# Power_Regulators.net
KiCad netlist of a schematic drawn in Altium Designer
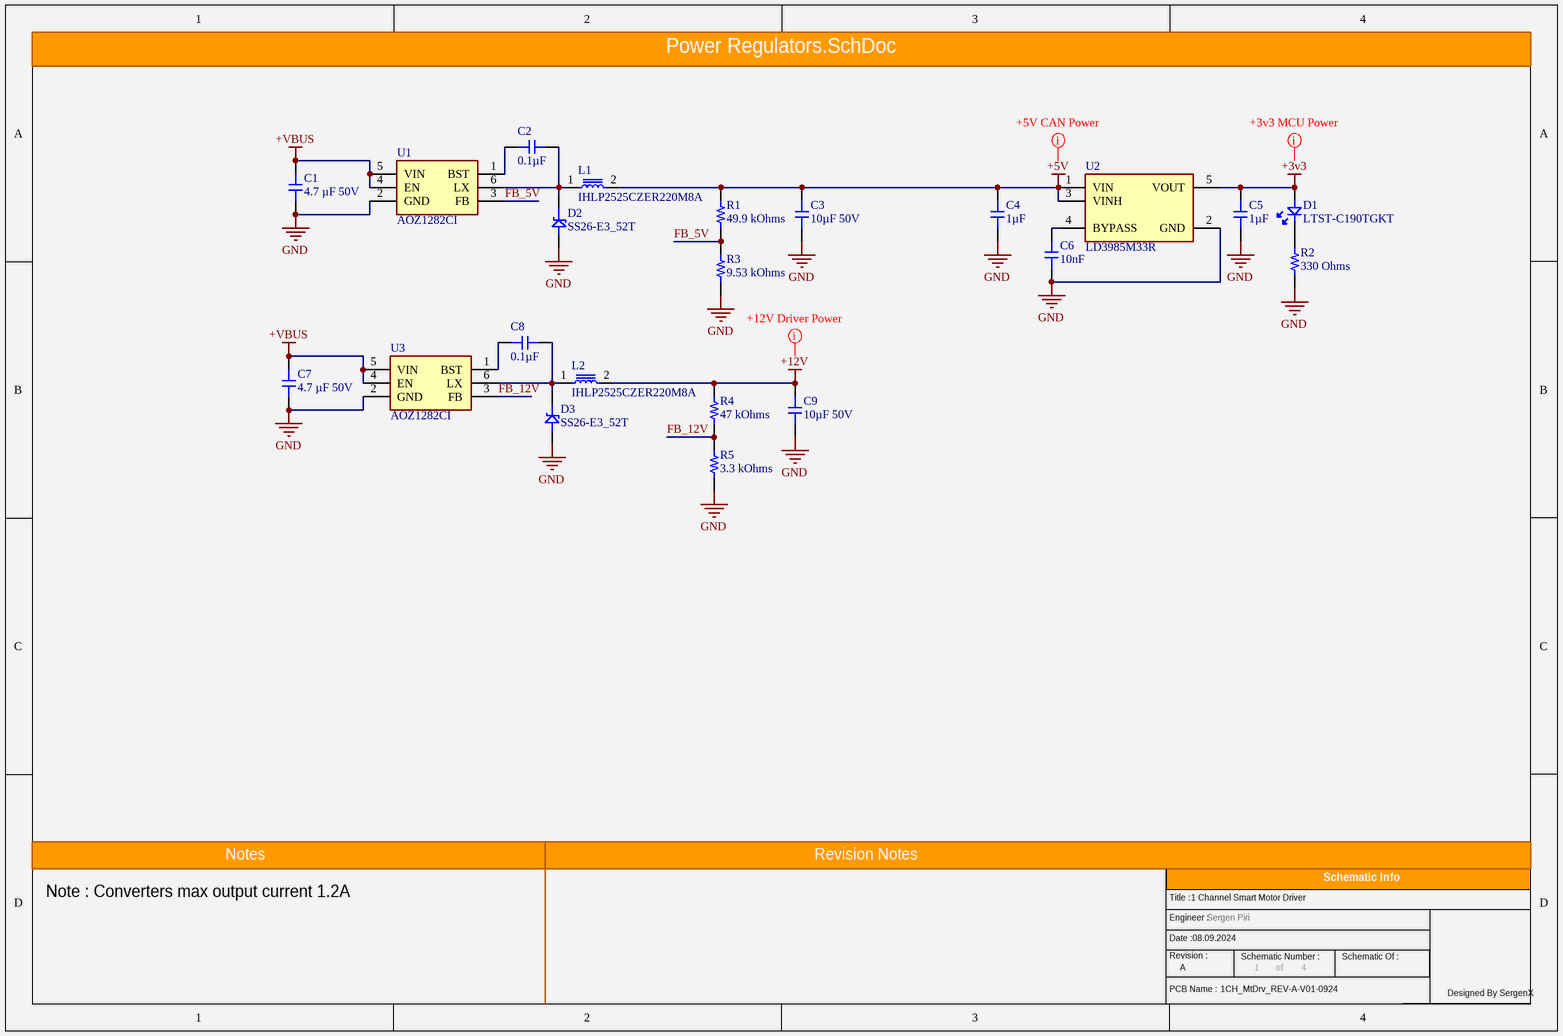
[diagram p0: Power Regulators.SchDoc]

(export (version "E")
  (design (tool "Eeschema 10.0.6"))
  (components
    (comp (ref "C1")
      (value "4.7 µF 50V")
      (footprint "1206_10uF")
      (description "10 uF 50V 1206")
      (libsource (lib "MainLibrary") (part "4.7 uF 50V 1206"))
    )
    (comp (ref "C2")
      (value "0.1µF")
      (footprint "0805")
      (description "0.1uF 0805 Surface Capacitor")
      (libsource (lib "MainLibrary") (part "0.1uF 0805 Surface Capacitor"))
    )
    (comp (ref "C3")
      (value "10µF 50V")
      (footprint "1206_10uF")
      (description "10 uF 50V 1206")
      (libsource (lib "MainLibrary") (part "10 uF 50V 1206"))
    )
    (comp (ref "C4")
      (value "1µF")
      (footprint "0603_Footprint")
      (description "1uF 0603 Surface Capacitor")
      (libsource (lib "MainLibrary") (part "1uF 0603 Surface Capacitor"))
    )
    (comp (ref "C5")
      (value "1µF")
      (footprint "0603_Footprint")
      (description "1uF 0603 Surface Capacitor")
      (libsource (lib "MainLibrary") (part "1uF 0603 Surface Capacitor"))
    )
    (comp (ref "C6")
      (value "10nF")
      (footprint "0603_Footprint")
      (description "10nF 0603 Surface Capacitor")
      (libsource (lib "MainLibrary") (part "10nF 0603 Surface Capacitor"))
    )
    (comp (ref "C7")
      (value "4.7 µF 50V")
      (footprint "1206_10uF")
      (description "10 uF 50V 1206")
      (libsource (lib "MainLibrary") (part "4.7 uF 50V 1206"))
    )
    (comp (ref "C8")
      (value "0.1µF")
      (footprint "0805")
      (description "0.1uF 0805 Surface Capacitor")
      (libsource (lib "MainLibrary") (part "0.1uF 0805 Surface Capacitor"))
    )
    (comp (ref "C9")
      (value "10µF 50V")
      (footprint "1206_10uF")
      (description "10 uF 50V 1206")
      (libsource (lib "MainLibrary") (part "10 uF 50V 1206"))
    )
    (comp (ref "D1")
      (value "LTST-C190TGKT")
      (footprint "LEDC1608X80N")
      (description "20mA Generic 0603 Led SMD")
      (fields
        (field (name "MANUFACTURER_PART_NUMBER") "LTST-C190KRKT")
        (field (name "MOUSER PART NUMBER") "859-LTST-C190KRKT")
      )
      (libsource (lib "MainLibrary") (part "LTST-C190TGKT"))
    )
    (comp (ref "D2")
      (value "SS26-E3_52T")
      (footprint "DIOM5436X244N")
      (description "2A SMD Schottky Diode")
      (fields
        (field (name "MANUFACTURER_PART_NUMBER") "SS26-E3/52T")
        (field (name "MOUSER PART NUMBER") "625-SS26-E3")
      )
      (libsource (lib "MainLibrary") (part "SS26-E3_52T"))
    )
    (comp (ref "D3")
      (value "SS26-E3_52T")
      (footprint "DIOM5436X244N")
      (description "2A SMD Schottky Diode")
      (fields
        (field (name "MANUFACTURER_PART_NUMBER") "SS26-E3/52T")
        (field (name "MOUSER PART NUMBER") "625-SS26-E3")
      )
      (libsource (lib "MainLibrary") (part "SS26-E3_52T"))
    )
    (comp (ref "L1")
      (value "IHLP2525CZER220M8A")
      (footprint "INDPM6965X300N")
      (description "Fixed Inductor 22uH 2.8A 174 mOHM SMD")
      (fields (field (name "MOUSER PART NUMBER") "70-IHLP2525CZR220M8A"))
      (libsource (lib "MainLibrary") (part "IHLP2525CZER220M8A"))
    )
    (comp (ref "L2")
      (value "IHLP2525CZER220M8A")
      (footprint "INDPM6965X300N")
      (description "Fixed Inductor 22uH 2.8A 174 mOHM SMD")
      (fields (field (name "MOUSER PART NUMBER") "70-IHLP2525CZR220M8A"))
      (libsource (lib "MainLibrary") (part "IHLP2525CZER220M8A"))
    )
    (comp (ref "R1")
      (value "49.9 kOhms")
      (footprint "0603_RES")
      (description "49.9 kOhms 0603")
      (libsource (lib "MainLibrary") (part "49.9 kOhms 0603"))
    )
    (comp (ref "R2")
      (value "330 Ohms")
      (footprint "0603_RES")
      (description "330 Ohm 0603")
      (libsource (lib "MainLibrary") (part "330 Ohm 0603"))
    )
    (comp (ref "R3")
      (value "9.53 kOhms")
      (footprint "0603_RES")
      (description "9.53 kOhms 0603")
      (libsource (lib "MainLibrary") (part "9.53 kOhms 0603"))
    )
    (comp (ref "R4")
      (value "47 kOhms")
      (footprint "0603_RES")
      (description "47 kOhm 0603")
      (libsource (lib "MainLibrary") (part "47 kOhms 0603"))
    )
    (comp (ref "R5")
      (value "3.3 kOhms")
      (footprint "0603_RES")
      (description "3.3 kOhms 0603")
      (libsource (lib "MainLibrary") (part "3.3 kOhms 0603"))
    )
    (comp (ref "U1")
      (value "AOZ1282CI")
      (footprint "SOT95P280X125-6N")
      (description "+36V 1.2A Buck Converter")
      (libsource (lib "MainLibrary") (part "AOZ1282CI"))
    )
    (comp (ref "U2")
      (value "LD3985M33R")
      (footprint "MainLibrary:SOT95P280X145-5N")
      (description "IC REG LIN 3.3V 150MA TSOT23-5")
      (libsource (lib "MainLibrary") (part "LD3985M33R"))
    )
    (comp (ref "U3")
      (value "AOZ1282CI")
      (footprint "SOT95P280X125-6N")
      (description "+36V 1.2A Buck Converter")
      (libsource (lib "MainLibrary") (part "AOZ1282CI"))
    )
  )
  (nets
    (net (code "1") (name "+3v3") (class "Default")
      (node (ref "C5") (pin "1") (pinfunction "1_1") (pintype "passive"))
      (node (ref "D1") (pin "2") (pinfunction "A_2") (pintype "passive"))
      (node (ref "U2") (pin "5") (pinfunction "VOUT_5") (pintype "passive"))
    )
    (net (code "2") (name "+5V") (class "Default")
      (node (ref "C3") (pin "1") (pinfunction "1_1") (pintype "passive"))
      (node (ref "C4") (pin "1") (pinfunction "1_1") (pintype "passive"))
      (node (ref "L1") (pin "2") (pinfunction "2_2") (pintype "passive"))
      (node (ref "R1") (pin "2") (pinfunction "2_2") (pintype "passive"))
      (node (ref "U2") (pin "1") (pinfunction "VIN_1") (pintype "passive"))
      (node (ref "U2") (pin "3") (pinfunction "VINH_3") (pintype "passive"))
    )
    (net (code "3") (name "+12V") (class "Default")
      (node (ref "C9") (pin "1") (pinfunction "1_1") (pintype "passive"))
      (node (ref "L2") (pin "2") (pinfunction "2_2") (pintype "passive"))
      (node (ref "R4") (pin "2") (pinfunction "2_2") (pintype "passive"))
    )
    (net (code "4") (name "+VBUS") (class "Default")
      (node (ref "C1") (pin "1") (pinfunction "1_1") (pintype "passive"))
      (node (ref "C7") (pin "1") (pinfunction "1_1") (pintype "passive"))
      (node (ref "U1") (pin "4") (pinfunction "EN_4") (pintype "passive"))
      (node (ref "U1") (pin "5") (pinfunction "VIN_5") (pintype "passive"))
      (node (ref "U3") (pin "4") (pinfunction "EN_4") (pintype "passive"))
      (node (ref "U3") (pin "5") (pinfunction "VIN_5") (pintype "passive"))
    )
    (net (code "5") (name "/FB_5V") (class "Default")
      (node (ref "R1") (pin "1") (pinfunction "1_1") (pintype "passive"))
      (node (ref "R3") (pin "2") (pinfunction "2_2") (pintype "passive"))
      (node (ref "U1") (pin "3") (pinfunction "FB_3") (pintype "passive"))
    )
    (net (code "6") (name "/FB_12V") (class "Default")
      (node (ref "R4") (pin "1") (pinfunction "1_1") (pintype "passive"))
      (node (ref "R5") (pin "2") (pinfunction "2_2") (pintype "passive"))
      (node (ref "U3") (pin "3") (pinfunction "FB_3") (pintype "passive"))
    )
    (net (code "7") (name "GND") (class "Default")
      (node (ref "C1") (pin "2") (pinfunction "2_2") (pintype "passive"))
      (node (ref "C3") (pin "2") (pinfunction "2_2") (pintype "passive"))
      (node (ref "C4") (pin "2") (pinfunction "2_2") (pintype "passive"))
      (node (ref "C5") (pin "2") (pinfunction "2_2") (pintype "passive"))
      (node (ref "C6") (pin "2") (pinfunction "2_2") (pintype "passive"))
      (node (ref "C7") (pin "2") (pinfunction "2_2") (pintype "passive"))
      (node (ref "C9") (pin "2") (pinfunction "2_2") (pintype "passive"))
      (node (ref "D2") (pin "2") (pinfunction "A_2") (pintype "passive"))
      (node (ref "D3") (pin "2") (pinfunction "A_2") (pintype "passive"))
      (node (ref "R2") (pin "1") (pinfunction "1_1") (pintype "passive"))
      (node (ref "R3") (pin "1") (pinfunction "1_1") (pintype "passive"))
      (node (ref "R5") (pin "1") (pinfunction "1_1") (pintype "passive"))
      (node (ref "U1") (pin "2") (pinfunction "GND_2") (pintype "passive"))
      (node (ref "U2") (pin "2") (pinfunction "GND_2") (pintype "power_in"))
      (node (ref "U3") (pin "2") (pinfunction "GND_2") (pintype "passive"))
    )
    (net (code "8") (name "Net-(D1-K)") (class "Default")
      (node (ref "D1") (pin "1") (pinfunction "K_1") (pintype "passive"))
      (node (ref "R2") (pin "2") (pinfunction "2_2") (pintype "passive"))
    )
    (net (code "9") (name "Net-(D2-K)") (class "Default")
      (node (ref "C2") (pin "2") (pinfunction "2_2") (pintype "passive"))
      (node (ref "D2") (pin "1") (pinfunction "K_1") (pintype "passive"))
      (node (ref "L1") (pin "1") (pinfunction "1_1") (pintype "passive"))
      (node (ref "U1") (pin "6") (pinfunction "LX_6") (pintype "passive"))
    )
    (net (code "10") (name "Net-(D3-K)") (class "Default")
      (node (ref "C8") (pin "2") (pinfunction "2_2") (pintype "passive"))
      (node (ref "D3") (pin "1") (pinfunction "K_1") (pintype "passive"))
      (node (ref "L2") (pin "1") (pinfunction "1_1") (pintype "passive"))
      (node (ref "U3") (pin "6") (pinfunction "LX_6") (pintype "passive"))
    )
    (net (code "11") (name "Net-(U1-BST)") (class "Default")
      (node (ref "C2") (pin "1") (pinfunction "1_1") (pintype "passive"))
      (node (ref "U1") (pin "1") (pinfunction "BST_1") (pintype "passive"))
    )
    (net (code "12") (name "Net-(U2-BYPASS)") (class "Default")
      (node (ref "C6") (pin "1") (pinfunction "1_1") (pintype "passive"))
      (node (ref "U2") (pin "4") (pinfunction "BYPASS_4") (pintype "passive"))
    )
    (net (code "13") (name "Net-(U3-BST)") (class "Default")
      (node (ref "C8") (pin "1") (pinfunction "1_1") (pintype "passive"))
      (node (ref "U3") (pin "1") (pinfunction "BST_1") (pintype "passive"))
    )
  )
)
